# latchupWatchdog.net
KiCad netlist of a schematic drawn in EAGLE
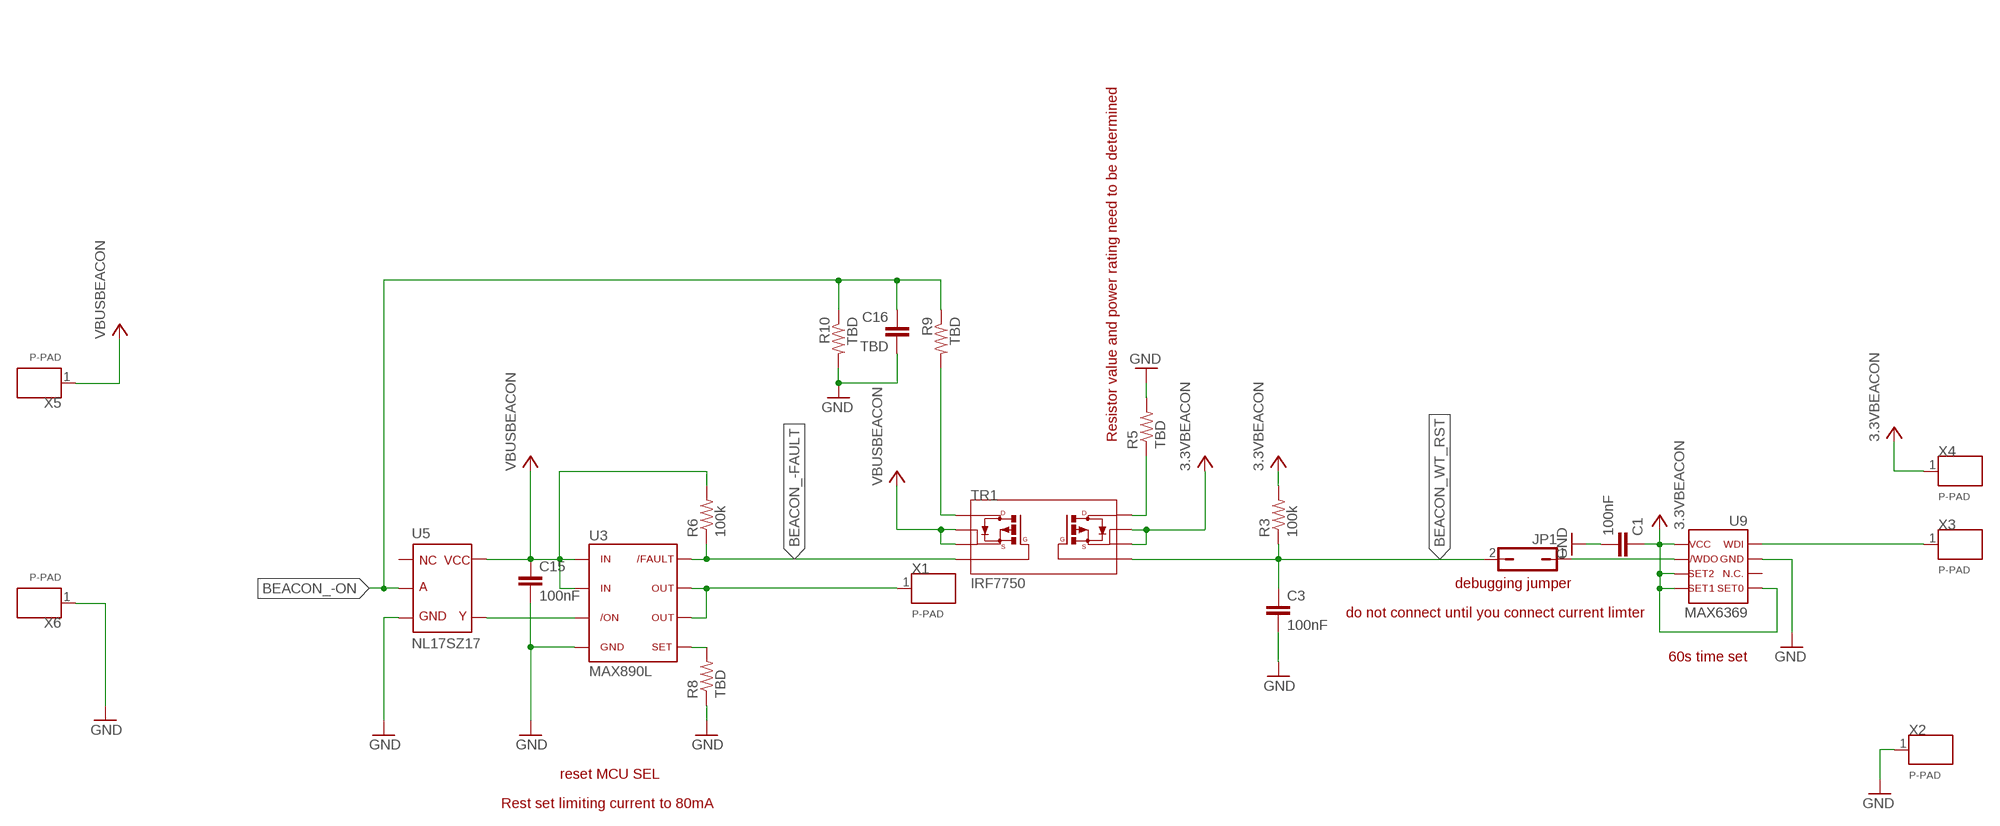
[diagram p0: schematic, sheet 1]

(export (version "E")
  (design (tool "Eeschema 10.0.6"))
  (components
    (comp (ref "C1")
      (value "100nF")
      (footprint "eagle-import:C0603(1608)")
      (libsource (lib "eagle-import") (part "C0603(1608)"))
    )
    (comp (ref "C3")
      (value "100nF")
      (footprint "eagle-import:C0603(1608)")
      (libsource (lib "eagle-import") (part "C0603(1608)"))
    )
    (comp (ref "C15")
      (value "100nF")
      (footprint "eagle-import:C0603(1608)")
      (libsource (lib "eagle-import") (part "C0603(1608)"))
    )
    (comp (ref "C16")
      (value "TBD")
      (footprint "eagle-import:C0603(1608)")
      (libsource (lib "eagle-import") (part "C0603(1608)"))
    )
    (comp (ref "JP1")
      (value "JP1Q")
      (footprint "eagle-import:JP1")
      (libsource (lib "eagle-import") (part "JP1Q"))
    )
    (comp (ref "R3")
      (value "100k")
      (footprint "eagle-import:R0603(1608)")
      (libsource (lib "eagle-import") (part "R0603(1608)"))
    )
    (comp (ref "R5")
      (value "TBD")
      (footprint "eagle-import:R0805(2012)")
      (libsource (lib "eagle-import") (part "R0805(2012)"))
    )
    (comp (ref "R6")
      (value "100k")
      (footprint "eagle-import:R0603(1608)")
      (libsource (lib "eagle-import") (part "R0603(1608)"))
    )
    (comp (ref "R8")
      (value "TBD")
      (footprint "eagle-import:R0603(1608)")
      (libsource (lib "eagle-import") (part "R0603(1608)"))
    )
    (comp (ref "R9")
      (value "TBD")
      (footprint "eagle-import:R0603(1608)")
      (libsource (lib "eagle-import") (part "R0603(1608)"))
    )
    (comp (ref "R10")
      (value "TBD")
      (footprint "eagle-import:R0603(1608)")
      (libsource (lib "eagle-import") (part "R0603(1608)"))
    )
    (comp (ref "TR1")
      (value "IRF7750")
      (footprint "eagle-import:TSSOP-8")
      (libsource (lib "eagle-import") (part "IRF7750"))
    )
    (comp (ref "U3")
      (value "MAX890L")
      (footprint "eagle-import:SO8")
      (libsource (lib "eagle-import") (part "MAX890L"))
    )
    (comp (ref "U5")
      (value "NL17SZ17")
      (footprint "eagle-import:SOT-553")
      (libsource (lib "eagle-import") (part "NL17SZ17"))
    )
    (comp (ref "U9")
      (value "MAX6369")
      (footprint "eagle-import:SOT23-8")
      (libsource (lib "eagle-import") (part "MAX6369"))
    )
    (comp (ref "X1")
      (value "P-PAD")
      (footprint "eagle-import:P-PAD")
      (libsource (lib "eagle-import") (part "P-PAD"))
    )
    (comp (ref "X2")
      (value "P-PAD")
      (footprint "eagle-import:P-PAD")
      (libsource (lib "eagle-import") (part "P-PAD"))
    )
    (comp (ref "X3")
      (value "P-PAD")
      (footprint "eagle-import:P-PAD")
      (libsource (lib "eagle-import") (part "P-PAD"))
    )
    (comp (ref "X4")
      (value "P-PAD")
      (footprint "eagle-import:P-PAD")
      (libsource (lib "eagle-import") (part "P-PAD"))
    )
    (comp (ref "X5")
      (value "P-PAD")
      (footprint "eagle-import:P-PAD")
      (libsource (lib "eagle-import") (part "P-PAD"))
    )
    (comp (ref "X6")
      (value "P-PAD")
      (footprint "eagle-import:P-PAD")
      (libsource (lib "eagle-import") (part "P-PAD"))
    )
  )
  (nets
    (net (code "1") (name "3.3VBEACON") (class "Default")
      (node (ref "C1") (pin "1") (pinfunction "1_1") (pintype "passive"))
      (node (ref "R3") (pin "2") (pinfunction "2_2") (pintype "passive"))
      (node (ref "TR1") (pin "6") (pinfunction "6_6") (pintype "passive"))
      (node (ref "TR1") (pin "7") (pinfunction "7_7") (pintype "passive"))
      (node (ref "U9") (pin "4") (pinfunction "P$4_4") (pintype "passive"))
      (node (ref "U9") (pin "5") (pinfunction "P$5_5") (pintype "passive"))
      (node (ref "U9") (pin "6") (pinfunction "P$6_6") (pintype "passive"))
      (node (ref "U9") (pin "8") (pinfunction "P$8_8") (pintype "power_in"))
      (node (ref "X4") (pin "1") (pinfunction "P$1_1") (pintype "bidirectional"))
    )
    (net (code "2") (name "BEACON_-FAULT") (class "Default")
      (node (ref "R6") (pin "1") (pinfunction "1_1") (pintype "passive"))
      (node (ref "TR1") (pin "4") (pinfunction "4_4") (pintype "passive"))
      (node (ref "U3") (pin "8") (pinfunction "P$8_8") (pintype "output"))
    )
    (net (code "3") (name "BEACON_-ON") (class "Default")
      (node (ref "C16") (pin "1") (pinfunction "1_1") (pintype "passive"))
      (node (ref "R10") (pin "1") (pinfunction "1_1") (pintype "passive"))
      (node (ref "R9") (pin "1") (pinfunction "1_1") (pintype "passive"))
      (node (ref "U5") (pin "2") (pinfunction "P$2_2") (pintype "input"))
    )
    (net (code "4") (name "BEACON_WT_RST") (class "Default")
      (node (ref "C3") (pin "1") (pinfunction "1_1") (pintype "passive"))
      (node (ref "JP1") (pin "2") (pinfunction "2_2") (pintype "passive"))
      (node (ref "R3") (pin "1") (pinfunction "1_1") (pintype "passive"))
      (node (ref "TR1") (pin "5") (pinfunction "5_5") (pintype "passive"))
    )
    (net (code "5") (name "GND") (class "Default")
      (node (ref "C1") (pin "2") (pinfunction "2_2") (pintype "passive"))
      (node (ref "C15") (pin "2") (pinfunction "2_2") (pintype "passive"))
      (node (ref "C16") (pin "2") (pinfunction "2_2") (pintype "passive"))
      (node (ref "C3") (pin "2") (pinfunction "2_2") (pintype "passive"))
      (node (ref "R10") (pin "2") (pinfunction "2_2") (pintype "passive"))
      (node (ref "R5") (pin "2") (pinfunction "2_2") (pintype "passive"))
      (node (ref "R8") (pin "1") (pinfunction "1_1") (pintype "passive"))
      (node (ref "U3") (pin "4") (pinfunction "P$4_4") (pintype "power_in"))
      (node (ref "U5") (pin "3") (pinfunction "P$3_3") (pintype "power_in"))
      (node (ref "U9") (pin "2") (pinfunction "P$2_2") (pintype "power_in"))
      (node (ref "X2") (pin "1") (pinfunction "P$1_1") (pintype "bidirectional"))
      (node (ref "X6") (pin "1") (pinfunction "P$1_1") (pintype "bidirectional"))
    )
    (net (code "6") (name "Net-(R5-Pad1)") (class "Default")
      (node (ref "R5") (pin "1") (pinfunction "1_1") (pintype "passive"))
      (node (ref "TR1") (pin "8") (pinfunction "8_8") (pintype "passive"))
    )
    (net (code "7") (name "Net-(R9-Pad2)") (class "Default")
      (node (ref "R9") (pin "2") (pinfunction "2_2") (pintype "passive"))
      (node (ref "TR1") (pin "1") (pinfunction "1_1") (pintype "passive"))
    )
    (net (code "8") (name "Net-(U3-P$3)") (class "Default")
      (node (ref "U3") (pin "3") (pinfunction "P$3_3") (pintype "input"))
      (node (ref "U5") (pin "4") (pinfunction "P$4_4") (pintype "output"))
    )
    (net (code "9") (name "Net-(U3-P$5)") (class "Default")
      (node (ref "R8") (pin "2") (pinfunction "2_2") (pintype "passive"))
      (node (ref "U3") (pin "5") (pinfunction "P$5_5") (pintype "passive"))
    )
    (net (code "10") (name "Net-(U3-P$6)") (class "Default")
      (node (ref "U3") (pin "6") (pinfunction "P$6_6") (pintype "output"))
      (node (ref "U3") (pin "7") (pinfunction "P$7_7") (pintype "output"))
      (node (ref "X1") (pin "1") (pinfunction "P$1_1") (pintype "bidirectional"))
    )
    (net (code "11") (name "Net-(U9-P$1)") (class "Default")
      (node (ref "U9") (pin "1") (pinfunction "P$1_1") (pintype "input"))
      (node (ref "X3") (pin "1") (pinfunction "P$1_1") (pintype "bidirectional"))
    )
    (net (code "12") (name "Net-(U9-P$7)") (class "Default")
      (node (ref "JP1") (pin "1") (pinfunction "1_1") (pintype "passive"))
      (node (ref "U9") (pin "7") (pinfunction "P$7_7") (pintype "output"))
    )
    (net (code "13") (name "VBUSBEACON") (class "Default")
      (node (ref "C15") (pin "1") (pinfunction "1_1") (pintype "passive"))
      (node (ref "R6") (pin "2") (pinfunction "2_2") (pintype "passive"))
      (node (ref "TR1") (pin "2") (pinfunction "2_2") (pintype "passive"))
      (node (ref "TR1") (pin "3") (pinfunction "3_3") (pintype "passive"))
      (node (ref "U3") (pin "1") (pinfunction "P$1_1") (pintype "input"))
      (node (ref "U3") (pin "2") (pinfunction "P$2_2") (pintype "input"))
      (node (ref "U5") (pin "5") (pinfunction "P$5_5") (pintype "power_in"))
      (node (ref "X5") (pin "1") (pinfunction "P$1_1") (pintype "bidirectional"))
    )
    (net (code "14") (name "unconnected-(U5-P$1-Pad1)") (class "Default")
      (node (ref "U5") (pin "1") (pinfunction "P$1_1") (pintype "no_connect"))
    )
    (net (code "15") (name "unconnected-(U9-P$3-Pad3)") (class "Default")
      (node (ref "U9") (pin "3") (pinfunction "P$3_3") (pintype "no_connect"))
    )
  )
)
